# groupe11finis2.net
KiCad netlist of a schematic drawn in EAGLE
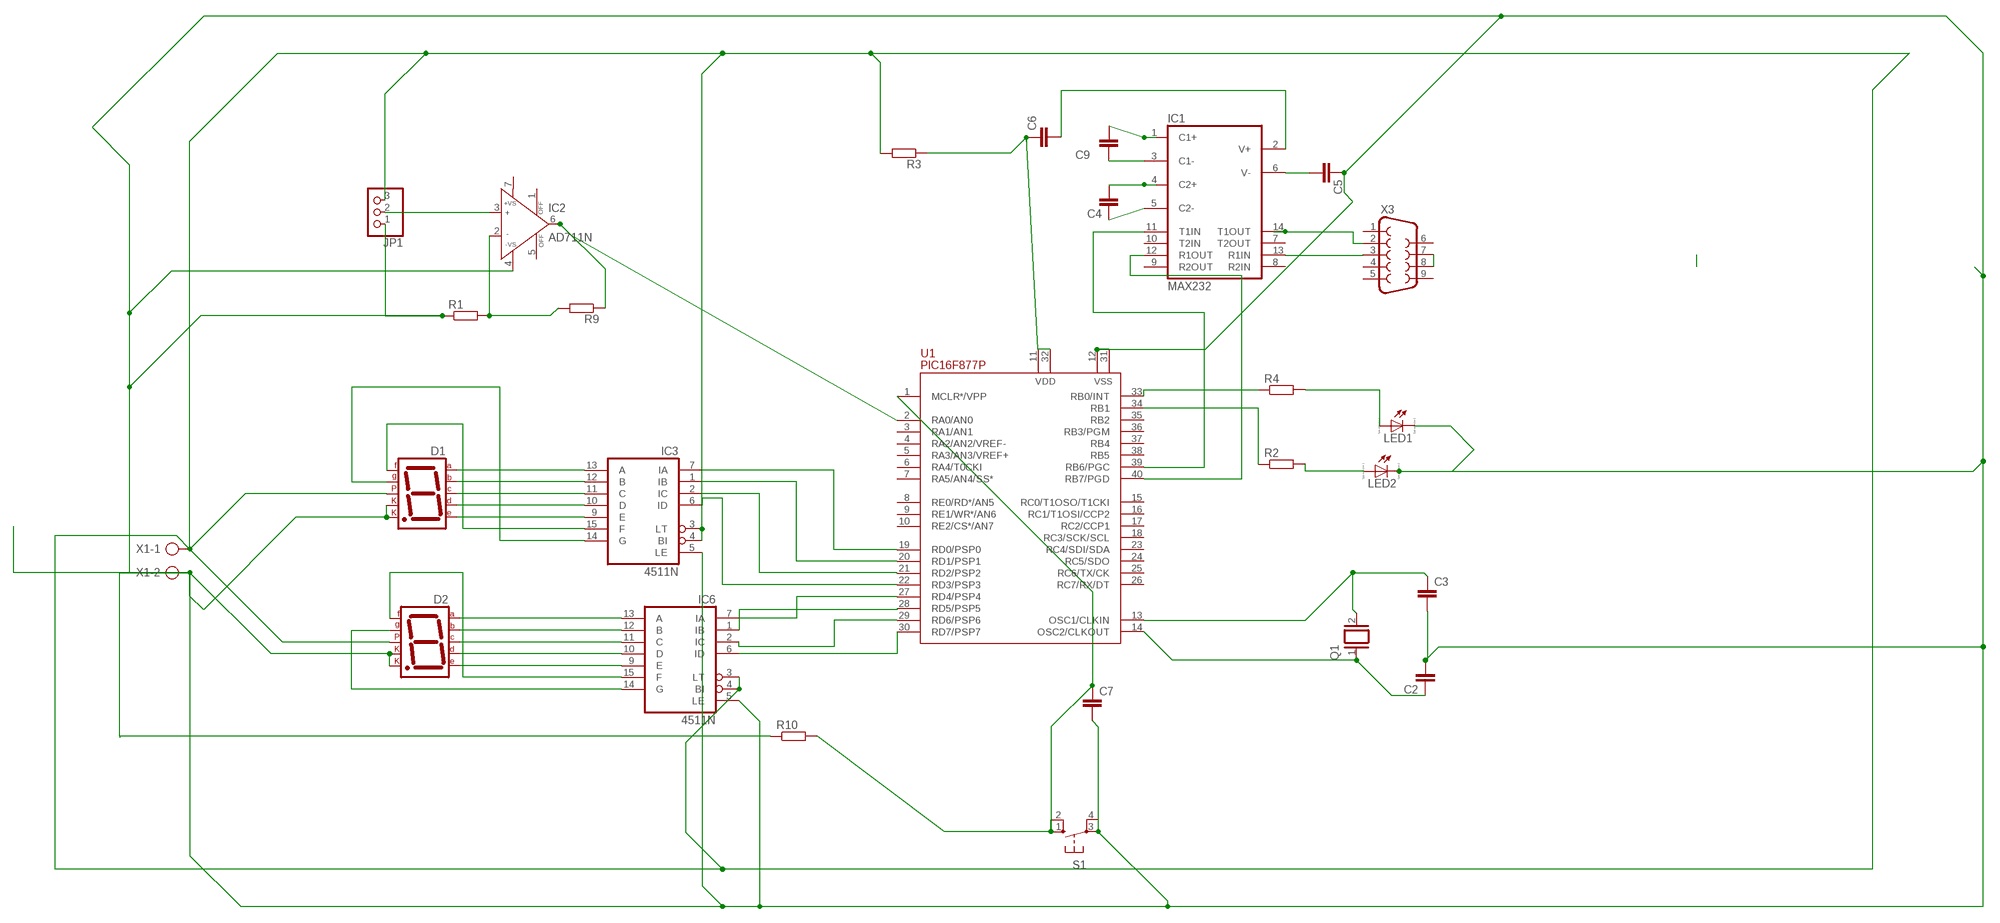
[diagram p0: schematic, sheet 1]

(export (version "E")
  (design (tool "Eeschema 10.0.6"))
  (components
    (comp (ref "C2")
      (value "C-EU025-024X044")
      (footprint "eagle-import:C025-024X044")
      (libsource (lib "eagle-import") (part "C-EU025-024X044"))
    )
    (comp (ref "C3")
      (value "C-EU025-024X044")
      (footprint "eagle-import:C025-024X044")
      (libsource (lib "eagle-import") (part "C-EU025-024X044"))
    )
    (comp (ref "C4")
      (value "C-EU025-024X044")
      (footprint "eagle-import:C025-024X044")
      (libsource (lib "eagle-import") (part "C-EU025-024X044"))
    )
    (comp (ref "C5")
      (value "C-EU025-024X044")
      (footprint "eagle-import:C025-024X044")
      (libsource (lib "eagle-import") (part "C-EU025-024X044"))
    )
    (comp (ref "C6")
      (value "C-EU025-024X044")
      (footprint "eagle-import:C025-024X044")
      (libsource (lib "eagle-import") (part "C-EU025-024X044"))
    )
    (comp (ref "C7")
      (value "C-EU025-024X044")
      (footprint "eagle-import:C025-024X044")
      (libsource (lib "eagle-import") (part "C-EU025-024X044"))
    )
    (comp (ref "C9")
      (value "C-EU025-024X044")
      (footprint "eagle-import:C025-024X044")
      (libsource (lib "eagle-import") (part "C-EU025-024X044"))
    )
    (comp (ref "D1")
      (value "7SEG-CK")
      (footprint "eagle-import:7SEG-13")
      (libsource (lib "eagle-import") (part "7SEG-CK"))
    )
    (comp (ref "D2")
      (value "7SEG-CK")
      (footprint "eagle-import:7SEG-13")
      (libsource (lib "eagle-import") (part "7SEG-CK"))
    )
    (comp (ref "IC1")
      (value "MAX232")
      (footprint "eagle-import:DIL16")
      (fields (field (name "MF") "MAXIM") (field (name "MPN") "MAX232ACPE+"))
      (libsource (lib "eagle-import") (part "MAX232"))
    )
    (comp (ref "IC2")
      (value "AD711N")
      (footprint "eagle-import:DIL08")
      (fields (field (name "MPN") "AD711BQ"))
      (libsource (lib "eagle-import") (part "AD711N"))
    )
    (comp (ref "IC3")
      (value "4511N")
      (footprint "eagle-import:DIL16")
      (libsource (lib "eagle-import") (part "4511N"))
    )
    (comp (ref "IC6")
      (value "4511N")
      (footprint "eagle-import:DIL16")
      (libsource (lib "eagle-import") (part "4511N"))
    )
    (comp (ref "JP1")
      (value "PINHD-1X3")
      (footprint "eagle-import:1X03")
      (libsource (lib "eagle-import") (part "PINHD-1X3"))
    )
    (comp (ref "LED1")
      (value "LED_ELD260")
      (footprint "eagle-import:LED_LD260")
      (libsource (lib "eagle-import") (part "LED_ELD260"))
    )
    (comp (ref "LED2")
      (value "LED_ELD260")
      (footprint "eagle-import:LED_LD260")
      (libsource (lib "eagle-import") (part "LED_ELD260"))
    )
    (comp (ref "Q1")
      (value "XTAL/S")
      (footprint "eagle-import:QS")
      (libsource (lib "eagle-import") (part "XTAL/S"))
    )
    (comp (ref "R1")
      (value "R-EU_0207/10")
      (footprint "eagle-import:0207_10")
      (libsource (lib "eagle-import") (part "R-EU_0207/10"))
    )
    (comp (ref "R2")
      (value "R-EU_0207/10")
      (footprint "eagle-import:0207_10")
      (libsource (lib "eagle-import") (part "R-EU_0207/10"))
    )
    (comp (ref "R3")
      (value "R-EU_0207/10")
      (footprint "eagle-import:0207_10")
      (libsource (lib "eagle-import") (part "R-EU_0207/10"))
    )
    (comp (ref "R4")
      (value "R-EU_0207/10")
      (footprint "eagle-import:0207_10")
      (libsource (lib "eagle-import") (part "R-EU_0207/10"))
    )
    (comp (ref "R9")
      (value "R-EU_0207/10")
      (footprint "eagle-import:0207_10")
      (libsource (lib "eagle-import") (part "R-EU_0207/10"))
    )
    (comp (ref "R10")
      (value "R-EU_0207/10")
      (footprint "eagle-import:0207_10")
      (libsource (lib "eagle-import") (part "R-EU_0207/10"))
    )
    (comp (ref "S1")
      (value "10-XX")
      (footprint "eagle-import:B3F-10XX")
      (fields (field (name "MPN") "B3F-1000"))
      (libsource (lib "eagle-import") (part "10-XX"))
    )
    (comp (ref "U1")
      (value "PIC16F877P")
      (footprint "eagle-import:DIL40")
      (libsource (lib "eagle-import") (part "PIC16F877P"))
    )
    (comp (ref "X1")
      (value "AK300/2")
      (footprint "eagle-import:AK300_2")
      (libsource (lib "eagle-import") (part "AK300/2"))
    )
    (comp (ref "X3")
      (value "F09V")
      (footprint "eagle-import:F09V")
      (libsource (lib "eagle-import") (part "F09V"))
    )
  )
  (nets
    (net (code "1") (name "Net-(C6-Pad1)") (class "Default")
      (node (ref "C6") (pin "1") (pinfunction "1_1") (pintype "passive"))
      (node (ref "R3") (pin "1") (pinfunction "1_1") (pintype "passive"))
      (node (ref "U1") (pin "11") (pinfunction "VDD_11") (pintype "bidirectional"))
      (node (ref "U1") (pin "32") (pinfunction "VDD_32") (pintype "bidirectional"))
    )
    (net (code "2") (name "Net-(D1-A)") (class "Default")
      (node (ref "D1") (pin "7") (pinfunction "A_7") (pintype "passive"))
      (node (ref "IC3") (pin "13") (pinfunction "A_13") (pintype "output"))
    )
    (net (code "3") (name "Net-(D1-B)") (class "Default")
      (node (ref "D1") (pin "6") (pinfunction "B_6") (pintype "passive"))
      (node (ref "IC3") (pin "12") (pinfunction "B_12") (pintype "output"))
    )
    (net (code "4") (name "Net-(D1-C)") (class "Default")
      (node (ref "D1") (pin "4") (pinfunction "C_4") (pintype "passive"))
      (node (ref "IC3") (pin "11") (pinfunction "C_11") (pintype "output"))
    )
    (net (code "5") (name "Net-(D1-CK1)") (class "Default")
      (node (ref "C2") (pin "2") (pinfunction "2_2") (pintype "passive"))
      (node (ref "C3") (pin "2") (pinfunction "2_2") (pintype "passive"))
      (node (ref "C5") (pin "1") (pinfunction "1_1") (pintype "passive"))
      (node (ref "C7") (pin "2") (pinfunction "2_2") (pintype "passive"))
      (node (ref "D1") (pin "3") (pinfunction "CK1_3") (pintype "passive"))
      (node (ref "D1") (pin "8") (pinfunction "CK2_8") (pintype "passive"))
      (node (ref "D2") (pin "3") (pinfunction "CK1_3") (pintype "passive"))
      (node (ref "D2") (pin "8") (pinfunction "CK2_8") (pintype "passive"))
      (node (ref "IC2") (pin "4") (pinfunction "-VS_4") (pintype "input"))
      (node (ref "IC3") (pin "5") (pinfunction "LE_5") (pintype "input"))
      (node (ref "IC6") (pin "5") (pinfunction "LE_5") (pintype "input"))
      (node (ref "JP1") (pin "1") (pinfunction "1_1") (pintype "passive"))
      (node (ref "LED1") (pin "K") (pinfunction "C_K") (pintype "passive"))
      (node (ref "LED2") (pin "K") (pinfunction "C_K") (pintype "passive"))
      (node (ref "R1") (pin "1") (pinfunction "1_1") (pintype "passive"))
      (node (ref "R10") (pin "1") (pinfunction "1_1") (pintype "passive"))
      (node (ref "S1") (pin "3") (pinfunction "P_3") (pintype "passive"))
      (node (ref "S1") (pin "4") (pinfunction "P1_4") (pintype "passive"))
      (node (ref "U1") (pin "12") (pinfunction "VSS_12") (pintype "bidirectional"))
      (node (ref "U1") (pin "31") (pinfunction "VSS_31") (pintype "bidirectional"))
      (node (ref "X1") (pin "2") (pinfunction "KL_2") (pintype "passive"))
    )
    (net (code "6") (name "Net-(D1-D)") (class "Default")
      (node (ref "D1") (pin "2") (pinfunction "D_2") (pintype "passive"))
      (node (ref "IC3") (pin "10") (pinfunction "D_10") (pintype "output"))
    )
    (net (code "7") (name "Net-(D1-DP)") (class "Default")
      (node (ref "D1") (pin "5") (pinfunction "DP_5") (pintype "passive"))
      (node (ref "D2") (pin "5") (pinfunction "DP_5") (pintype "passive"))
      (node (ref "IC3") (pin "3") (pinfunction "LT_3") (pintype "input"))
      (node (ref "IC3") (pin "4") (pinfunction "BI_4") (pintype "input"))
      (node (ref "IC6") (pin "3") (pinfunction "LT_3") (pintype "input"))
      (node (ref "IC6") (pin "4") (pinfunction "BI_4") (pintype "input"))
      (node (ref "JP1") (pin "3") (pinfunction "3_3") (pintype "passive"))
      (node (ref "R3") (pin "2") (pinfunction "2_2") (pintype "passive"))
      (node (ref "X1") (pin "1") (pinfunction "KL_1") (pintype "passive"))
    )
    (net (code "8") (name "Net-(D1-E)") (class "Default")
      (node (ref "D1") (pin "1") (pinfunction "E_1") (pintype "passive"))
      (node (ref "IC3") (pin "9") (pinfunction "E_9") (pintype "output"))
    )
    (net (code "9") (name "Net-(D1-F)") (class "Default")
      (node (ref "D1") (pin "9") (pinfunction "F_9") (pintype "passive"))
      (node (ref "IC3") (pin "15") (pinfunction "F_15") (pintype "output"))
    )
    (net (code "10") (name "Net-(D1-G)") (class "Default")
      (node (ref "D1") (pin "10") (pinfunction "G_10") (pintype "passive"))
      (node (ref "IC3") (pin "14") (pinfunction "G_14") (pintype "output"))
    )
    (net (code "11") (name "Net-(D2-A)") (class "Default")
      (node (ref "D2") (pin "7") (pinfunction "A_7") (pintype "passive"))
      (node (ref "IC6") (pin "13") (pinfunction "A_13") (pintype "output"))
    )
    (net (code "12") (name "Net-(D2-B)") (class "Default")
      (node (ref "D2") (pin "6") (pinfunction "B_6") (pintype "passive"))
      (node (ref "IC6") (pin "12") (pinfunction "B_12") (pintype "output"))
    )
    (net (code "13") (name "Net-(D2-C)") (class "Default")
      (node (ref "D2") (pin "4") (pinfunction "C_4") (pintype "passive"))
      (node (ref "IC6") (pin "11") (pinfunction "C_11") (pintype "output"))
    )
    (net (code "14") (name "Net-(D2-D)") (class "Default")
      (node (ref "D2") (pin "2") (pinfunction "D_2") (pintype "passive"))
      (node (ref "IC6") (pin "10") (pinfunction "D_10") (pintype "output"))
    )
    (net (code "15") (name "Net-(D2-E)") (class "Default")
      (node (ref "D2") (pin "1") (pinfunction "E_1") (pintype "passive"))
      (node (ref "IC6") (pin "9") (pinfunction "E_9") (pintype "output"))
    )
    (net (code "16") (name "Net-(D2-F)") (class "Default")
      (node (ref "D2") (pin "9") (pinfunction "F_9") (pintype "passive"))
      (node (ref "IC6") (pin "15") (pinfunction "F_15") (pintype "output"))
    )
    (net (code "17") (name "Net-(D2-G)") (class "Default")
      (node (ref "D2") (pin "10") (pinfunction "G_10") (pintype "passive"))
      (node (ref "IC6") (pin "14") (pinfunction "G_14") (pintype "output"))
    )
    (net (code "18") (name "Net-(IC1A-C1+)") (class "Default")
      (node (ref "C9") (pin "2") (pinfunction "2_2") (pintype "passive"))
      (node (ref "IC1") (pin "1") (pinfunction "C1+_1") (pintype "bidirectional"))
    )
    (net (code "19") (name "Net-(IC1A-C1-)") (class "Default")
      (node (ref "C9") (pin "1") (pinfunction "1_1") (pintype "passive"))
      (node (ref "IC1") (pin "3") (pinfunction "C1-_3") (pintype "bidirectional"))
    )
    (net (code "20") (name "Net-(IC1A-C2+)") (class "Default")
      (node (ref "C4") (pin "2") (pinfunction "2_2") (pintype "passive"))
      (node (ref "IC1") (pin "4") (pinfunction "C2+_4") (pintype "bidirectional"))
    )
    (net (code "21") (name "Net-(IC1A-C2-)") (class "Default")
      (node (ref "C4") (pin "1") (pinfunction "1_1") (pintype "passive"))
      (node (ref "IC1") (pin "5") (pinfunction "C2-_5") (pintype "bidirectional"))
    )
    (net (code "22") (name "Net-(IC1A-R1IN)") (class "Default")
      (node (ref "IC1") (pin "13") (pinfunction "R1IN_13") (pintype "input"))
      (node (ref "X3") (pin "3") (pinfunction "3_3") (pintype "passive"))
    )
    (net (code "23") (name "Net-(IC1A-R1OUT)") (class "Default")
      (node (ref "IC1") (pin "12") (pinfunction "R1OUT_12") (pintype "output"))
      (node (ref "U1") (pin "40") (pinfunction "RB7/PGD_40") (pintype "bidirectional"))
    )
    (net (code "24") (name "Net-(IC1A-T1IN)") (class "Default")
      (node (ref "IC1") (pin "11") (pinfunction "T1IN_11") (pintype "input"))
      (node (ref "U1") (pin "39") (pinfunction "RB6/PGC_39") (pintype "bidirectional"))
    )
    (net (code "25") (name "Net-(IC1A-T1OUT)") (class "Default")
      (node (ref "IC1") (pin "14") (pinfunction "T1OUT_14") (pintype "output"))
      (node (ref "X3") (pin "2") (pinfunction "2_2") (pintype "passive"))
    )
    (net (code "26") (name "Net-(IC1A-V+)") (class "Default")
      (node (ref "C6") (pin "2") (pinfunction "2_2") (pintype "passive"))
      (node (ref "IC1") (pin "2") (pinfunction "V+_2") (pintype "bidirectional"))
    )
    (net (code "27") (name "Net-(IC1A-V-)") (class "Default")
      (node (ref "C5") (pin "2") (pinfunction "2_2") (pintype "passive"))
      (node (ref "IC1") (pin "6") (pinfunction "V-_6") (pintype "bidirectional"))
    )
    (net (code "28") (name "Net-(IC2-IN+)") (class "Default")
      (node (ref "IC2") (pin "3") (pinfunction "IN+_3") (pintype "input"))
      (node (ref "JP1") (pin "2") (pinfunction "2_2") (pintype "passive"))
    )
    (net (code "29") (name "Net-(IC2-IN-)") (class "Default")
      (node (ref "IC2") (pin "2") (pinfunction "IN-_2") (pintype "input"))
      (node (ref "R1") (pin "2") (pinfunction "2_2") (pintype "passive"))
      (node (ref "R9") (pin "2") (pinfunction "2_2") (pintype "passive"))
    )
    (net (code "30") (name "Net-(IC2-OUT)") (class "Default")
      (node (ref "IC2") (pin "6") (pinfunction "OUT_6") (pintype "output"))
      (node (ref "R9") (pin "1") (pinfunction "1_1") (pintype "passive"))
      (node (ref "U1") (pin "2") (pinfunction "RA0/AN0_2") (pintype "bidirectional"))
    )
    (net (code "31") (name "Net-(IC3A-IA)") (class "Default")
      (node (ref "IC3") (pin "7") (pinfunction "IA_7") (pintype "input"))
      (node (ref "U1") (pin "19") (pinfunction "RD0/PSP0_19") (pintype "bidirectional"))
    )
    (net (code "32") (name "Net-(IC3A-IB)") (class "Default")
      (node (ref "IC3") (pin "1") (pinfunction "IB_1") (pintype "input"))
      (node (ref "U1") (pin "20") (pinfunction "RD1/PSP1_20") (pintype "bidirectional"))
    )
    (net (code "33") (name "Net-(IC3A-IC)") (class "Default")
      (node (ref "IC3") (pin "2") (pinfunction "IC_2") (pintype "input"))
      (node (ref "U1") (pin "21") (pinfunction "RD2/PSP2_21") (pintype "bidirectional"))
    )
    (net (code "34") (name "Net-(IC3A-ID)") (class "Default")
      (node (ref "IC3") (pin "6") (pinfunction "ID_6") (pintype "input"))
      (node (ref "U1") (pin "22") (pinfunction "RD3/PSP3_22") (pintype "bidirectional"))
    )
    (net (code "35") (name "Net-(IC6A-IA)") (class "Default")
      (node (ref "IC6") (pin "7") (pinfunction "IA_7") (pintype "input"))
      (node (ref "U1") (pin "27") (pinfunction "RD4/PSP4_27") (pintype "bidirectional"))
    )
    (net (code "36") (name "Net-(IC6A-IB)") (class "Default")
      (node (ref "IC6") (pin "1") (pinfunction "IB_1") (pintype "input"))
      (node (ref "U1") (pin "28") (pinfunction "RD5/PSP5_28") (pintype "bidirectional"))
    )
    (net (code "37") (name "Net-(IC6A-IC)") (class "Default")
      (node (ref "IC6") (pin "2") (pinfunction "IC_2") (pintype "input"))
      (node (ref "U1") (pin "29") (pinfunction "RD6/PSP6_29") (pintype "bidirectional"))
    )
    (net (code "38") (name "Net-(IC6A-ID)") (class "Default")
      (node (ref "IC6") (pin "6") (pinfunction "ID_6") (pintype "input"))
      (node (ref "U1") (pin "30") (pinfunction "RD7/PSP7_30") (pintype "bidirectional"))
    )
    (net (code "39") (name "Net-(LED1-PadA)") (class "Default")
      (node (ref "LED1") (pin "A") (pinfunction "A_A") (pintype "passive"))
      (node (ref "R4") (pin "2") (pinfunction "2_2") (pintype "passive"))
    )
    (net (code "40") (name "Net-(LED2-PadA)") (class "Default")
      (node (ref "LED2") (pin "A") (pinfunction "A_A") (pintype "passive"))
      (node (ref "R2") (pin "2") (pinfunction "2_2") (pintype "passive"))
    )
    (net (code "41") (name "Net-(S1-S)") (class "Default")
      (node (ref "C7") (pin "1") (pinfunction "1_1") (pintype "passive"))
      (node (ref "R10") (pin "2") (pinfunction "2_2") (pintype "passive"))
      (node (ref "S1") (pin "1") (pinfunction "S_1") (pintype "passive"))
      (node (ref "S1") (pin "2") (pinfunction "S1_2") (pintype "passive"))
      (node (ref "U1") (pin "1") (pinfunction "MCLR*/VPP_1") (pintype "input"))
    )
    (net (code "42") (name "Net-(U1-OSC1{slash}CLKIN)") (class "Default")
      (node (ref "C3") (pin "1") (pinfunction "1_1") (pintype "passive"))
      (node (ref "Q1") (pin "2") (pinfunction "2_2") (pintype "passive"))
      (node (ref "U1") (pin "13") (pinfunction "OSC1/CLKIN_13") (pintype "input"))
    )
    (net (code "43") (name "Net-(U1-OSC2{slash}CLKOUT)") (class "Default")
      (node (ref "C2") (pin "1") (pinfunction "1_1") (pintype "passive"))
      (node (ref "Q1") (pin "1") (pinfunction "1_1") (pintype "passive"))
      (node (ref "U1") (pin "14") (pinfunction "OSC2/CLKOUT_14") (pintype "output"))
    )
    (net (code "44") (name "Net-(U1-RB0{slash}INT)") (class "Default")
      (node (ref "R4") (pin "1") (pinfunction "1_1") (pintype "passive"))
      (node (ref "U1") (pin "33") (pinfunction "RB0/INT_33") (pintype "bidirectional"))
    )
    (net (code "45") (name "Net-(U1-RB1)") (class "Default")
      (node (ref "R2") (pin "1") (pinfunction "1_1") (pintype "passive"))
      (node (ref "U1") (pin "34") (pinfunction "RB1_34") (pintype "bidirectional"))
    )
    (net (code "46") (name "Net-(X3-Pad7)") (class "Default")
      (node (ref "X3") (pin "7") (pinfunction "7_7") (pintype "passive"))
      (node (ref "X3") (pin "8") (pinfunction "8_8") (pintype "passive"))
    )
    (net (code "47") (name "unconnected-(IC1A-R2IN-Pad8)") (class "Default")
      (node (ref "IC1") (pin "8") (pinfunction "R2IN_8") (pintype "input"))
    )
    (net (code "48") (name "unconnected-(IC1A-R2OUT-Pad9)") (class "Default")
      (node (ref "IC1") (pin "9") (pinfunction "R2OUT_9") (pintype "output"))
    )
    (net (code "49") (name "unconnected-(IC1A-T2IN-Pad10)") (class "Default")
      (node (ref "IC1") (pin "10") (pinfunction "T2IN_10") (pintype "input"))
    )
    (net (code "50") (name "unconnected-(IC1A-T2OUT-Pad7)") (class "Default")
      (node (ref "IC1") (pin "7") (pinfunction "T2OUT_7") (pintype "output"))
    )
    (net (code "51") (name "unconnected-(IC2-+VS-Pad7)") (class "Default")
      (node (ref "IC2") (pin "7") (pinfunction "+VS_7") (pintype "input"))
    )
    (net (code "52") (name "unconnected-(IC2-OFF-Pad1)") (class "Default")
      (node (ref "IC2") (pin "1") (pinfunction "OFF_1") (pintype "passive"))
    )
    (net (code "53") (name "unconnected-(IC2-OFF-Pad5)") (class "Default")
      (node (ref "IC2") (pin "5") (pinfunction "OFF_5") (pintype "passive"))
    )
    (net (code "54") (name "unconnected-(U1-RA1{slash}AN1-Pad3)") (class "Default")
      (node (ref "U1") (pin "3") (pinfunction "RA1/AN1_3") (pintype "bidirectional"))
    )
    (net (code "55") (name "unconnected-(U1-RA2{slash}AN2{slash}VREF--Pad4)") (class "Default")
      (node (ref "U1") (pin "4") (pinfunction "RA2/AN2/VREF-_4") (pintype "bidirectional"))
    )
    (net (code "56") (name "unconnected-(U1-RA3{slash}AN3{slash}VREF+-Pad5)") (class "Default")
      (node (ref "U1") (pin "5") (pinfunction "RA3/AN3/VREF+_5") (pintype "bidirectional"))
    )
    (net (code "57") (name "unconnected-(U1-RA4{slash}T0CKI-Pad6)") (class "Default")
      (node (ref "U1") (pin "6") (pinfunction "RA4/T0CKI_6") (pintype "bidirectional"))
    )
    (net (code "58") (name "unconnected-(U1-RA5{slash}AN4{slash}SS*-Pad7)") (class "Default")
      (node (ref "U1") (pin "7") (pinfunction "RA5/AN4/SS*_7") (pintype "bidirectional"))
    )
    (net (code "59") (name "unconnected-(U1-RB2-Pad35)") (class "Default")
      (node (ref "U1") (pin "35") (pinfunction "RB2_35") (pintype "bidirectional"))
    )
    (net (code "60") (name "unconnected-(U1-RB3{slash}PGM-Pad36)") (class "Default")
      (node (ref "U1") (pin "36") (pinfunction "RB3/PGM_36") (pintype "bidirectional"))
    )
    (net (code "61") (name "unconnected-(U1-RB4-Pad37)") (class "Default")
      (node (ref "U1") (pin "37") (pinfunction "RB4_37") (pintype "bidirectional"))
    )
    (net (code "62") (name "unconnected-(U1-RB5-Pad38)") (class "Default")
      (node (ref "U1") (pin "38") (pinfunction "RB5_38") (pintype "bidirectional"))
    )
    (net (code "63") (name "unconnected-(U1-RC0{slash}T1OSO{slash}T1CKI-Pad15)") (class "Default")
      (node (ref "U1") (pin "15") (pinfunction "RC0/T1OSO/T1CKI_15") (pintype "bidirectional"))
    )
    (net (code "64") (name "unconnected-(U1-RC1{slash}T1OSI{slash}CCP2-Pad16)") (class "Default")
      (node (ref "U1") (pin "16") (pinfunction "RC1/T1OSI/CCP2_16") (pintype "bidirectional"))
    )
    (net (code "65") (name "unconnected-(U1-RC2{slash}CCP1-Pad17)") (class "Default")
      (node (ref "U1") (pin "17") (pinfunction "RC2/CCP1_17") (pintype "bidirectional"))
    )
    (net (code "66") (name "unconnected-(U1-RC3{slash}SCK{slash}SCL-Pad18)") (class "Default")
      (node (ref "U1") (pin "18") (pinfunction "RC3/SCK/SCL_18") (pintype "bidirectional"))
    )
    (net (code "67") (name "unconnected-(U1-RC4{slash}SDI{slash}SDA-Pad23)") (class "Default")
      (node (ref "U1") (pin "23") (pinfunction "RC4/SDI/SDA_23") (pintype "bidirectional"))
    )
    (net (code "68") (name "unconnected-(U1-RC5{slash}SDO-Pad24)") (class "Default")
      (node (ref "U1") (pin "24") (pinfunction "RC5/SDO_24") (pintype "bidirectional"))
    )
    (net (code "69") (name "unconnected-(U1-RC6{slash}TX{slash}CK-Pad25)") (class "Default")
      (node (ref "U1") (pin "25") (pinfunction "RC6/TX/CK_25") (pintype "bidirectional"))
    )
    (net (code "70") (name "unconnected-(U1-RC7{slash}RX{slash}DT-Pad26)") (class "Default")
      (node (ref "U1") (pin "26") (pinfunction "RC7/RX/DT_26") (pintype "bidirectional"))
    )
    (net (code "71") (name "unconnected-(U1-RE0{slash}RD*{slash}AN5-Pad8)") (class "Default")
      (node (ref "U1") (pin "8") (pinfunction "RE0/RD*/AN5_8") (pintype "bidirectional"))
    )
    (net (code "72") (name "unconnected-(U1-RE1{slash}WR*{slash}AN6-Pad9)") (class "Default")
      (node (ref "U1") (pin "9") (pinfunction "RE1/WR*/AN6_9") (pintype "bidirectional"))
    )
    (net (code "73") (name "unconnected-(U1-RE2{slash}CS*{slash}AN7-Pad10)") (class "Default")
      (node (ref "U1") (pin "10") (pinfunction "RE2/CS*/AN7_10") (pintype "bidirectional"))
    )
    (net (code "74") (name "unconnected-(X3-Pad1)") (class "Default")
      (node (ref "X3") (pin "1") (pinfunction "1_1") (pintype "passive"))
    )
    (net (code "75") (name "unconnected-(X3-Pad4)") (class "Default")
      (node (ref "X3") (pin "4") (pinfunction "4_4") (pintype "passive"))
    )
    (net (code "76") (name "unconnected-(X3-Pad5)") (class "Default")
      (node (ref "X3") (pin "5") (pinfunction "5_5") (pintype "passive"))
    )
    (net (code "77") (name "unconnected-(X3-Pad6)") (class "Default")
      (node (ref "X3") (pin "6") (pinfunction "6_6") (pintype "passive"))
    )
    (net (code "78") (name "unconnected-(X3-Pad9)") (class "Default")
      (node (ref "X3") (pin "9") (pinfunction "9_9") (pintype "passive"))
    )
  )
)
